# digital.net
KiCad netlist of a schematic drawn in EAGLE
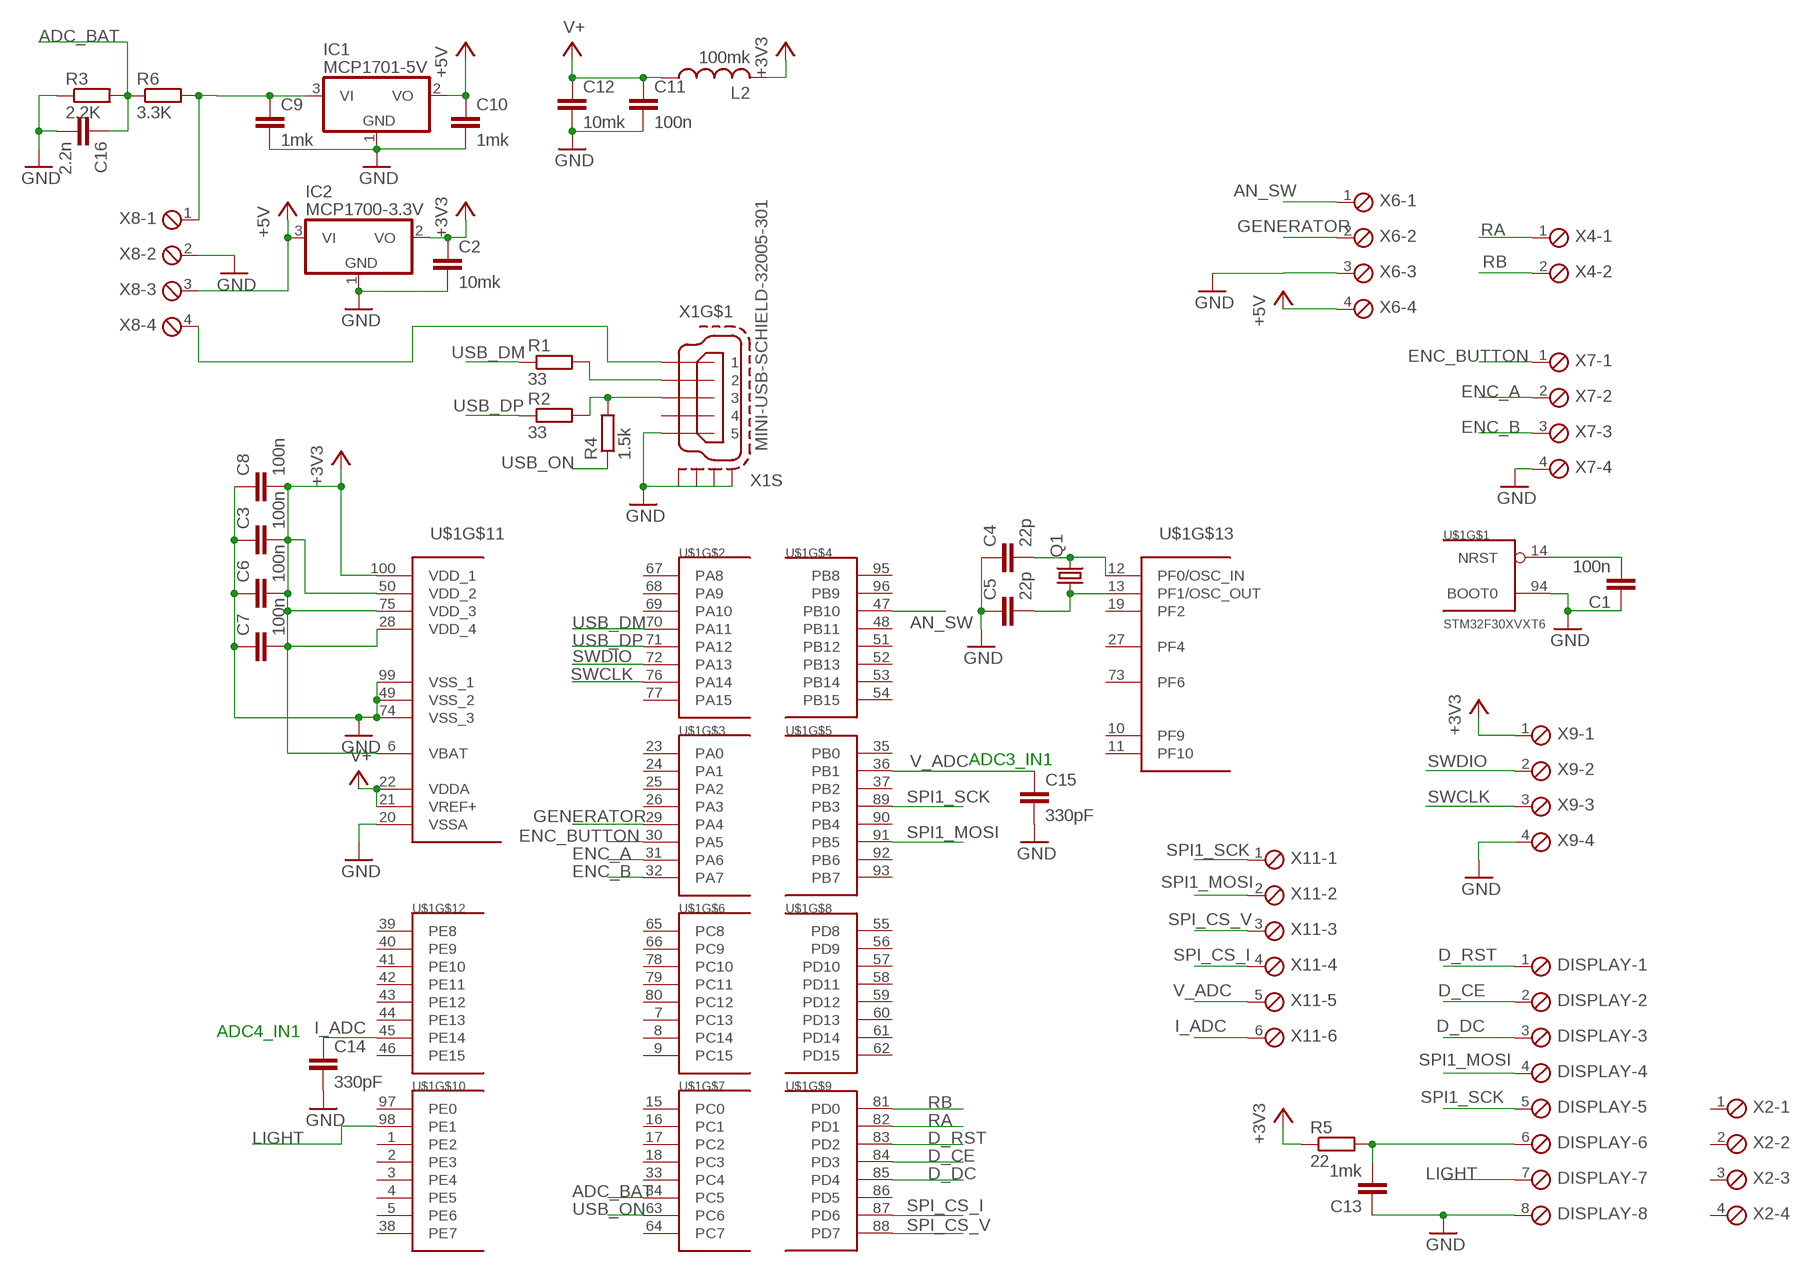
[diagram p0: schematic, sheet 1]

(export (version "E")
  (design (tool "Eeschema 10.0.6"))
  (components
    (comp (ref "C1")
      (value "100n")
      (footprint "eagle-import:C0603")
      (libsource (lib "eagle-import") (part "C-EUC0603"))
    )
    (comp (ref "C2")
      (value "10mk")
      (footprint "eagle-import:C0805")
      (libsource (lib "eagle-import") (part "C-EUC0805"))
    )
    (comp (ref "C3")
      (value "100n")
      (footprint "eagle-import:C0603")
      (libsource (lib "eagle-import") (part "C-EUC0603"))
    )
    (comp (ref "C4")
      (value "22p")
      (footprint "eagle-import:C0805")
      (libsource (lib "eagle-import") (part "C-EUC0805"))
    )
    (comp (ref "C5")
      (value "22p")
      (footprint "eagle-import:C0805")
      (libsource (lib "eagle-import") (part "C-EUC0805"))
    )
    (comp (ref "C6")
      (value "100n")
      (footprint "eagle-import:C0603")
      (libsource (lib "eagle-import") (part "C-EUC0603"))
    )
    (comp (ref "C7")
      (value "100n")
      (footprint "eagle-import:C0603")
      (libsource (lib "eagle-import") (part "C-EUC0603"))
    )
    (comp (ref "C8")
      (value "100n")
      (footprint "eagle-import:C0603")
      (libsource (lib "eagle-import") (part "C-EUC0603"))
    )
    (comp (ref "C9")
      (value "1mk")
      (footprint "eagle-import:C0603")
      (libsource (lib "eagle-import") (part "C-EUC0603"))
    )
    (comp (ref "C10")
      (value "1mk")
      (footprint "eagle-import:C0603")
      (libsource (lib "eagle-import") (part "C-EUC0603"))
    )
    (comp (ref "C11")
      (value "100n")
      (footprint "eagle-import:C0603")
      (libsource (lib "eagle-import") (part "C-EUC0603"))
    )
    (comp (ref "C12")
      (value "10mk")
      (footprint "eagle-import:C0805")
      (libsource (lib "eagle-import") (part "C-EUC0805"))
    )
    (comp (ref "C13")
      (value "1mk")
      (footprint "eagle-import:C0603")
      (libsource (lib "eagle-import") (part "C-EUC0603"))
    )
    (comp (ref "C14")
      (value "330pF")
      (footprint "eagle-import:C0805")
      (libsource (lib "eagle-import") (part "C-EUC0805"))
    )
    (comp (ref "C15")
      (value "330pF")
      (footprint "eagle-import:C0805")
      (libsource (lib "eagle-import") (part "C-EUC0805"))
    )
    (comp (ref "C16")
      (value "2.2n")
      (footprint "eagle-import:C0805")
      (libsource (lib "eagle-import") (part "C-EUC0805"))
    )
    (comp (ref "DISPLAY")
      (value "MPT8")
      (footprint "eagle-import:8POL254")
      (libsource (lib "eagle-import") (part "MPT8"))
    )
    (comp (ref "IC1")
      (value "MCP1701-5V")
      (footprint "eagle-import:SOT23")
      (libsource (lib "eagle-import") (part "MCP1703CB"))
    )
    (comp (ref "IC2")
      (value "MCP1700-3.3V")
      (footprint "eagle-import:SOT23")
      (libsource (lib "eagle-import") (part "MCP1703CB"))
    )
    (comp (ref "L2")
      (value "100mk")
      (footprint "eagle-import:0204_7")
      (libsource (lib "eagle-import") (part "L-US0204/7"))
    )
    (comp (ref "Q1")
      (value "CRYSTALHC49UP")
      (footprint "eagle-import:HC49UP")
      (libsource (lib "eagle-import") (part "CRYSTALHC49UP"))
    )
    (comp (ref "R1")
      (value "33")
      (footprint "eagle-import:R0603")
      (libsource (lib "eagle-import") (part "R-EU_R0603"))
    )
    (comp (ref "R2")
      (value "33")
      (footprint "eagle-import:R0603")
      (libsource (lib "eagle-import") (part "R-EU_R0603"))
    )
    (comp (ref "R3")
      (value "2.2K")
      (footprint "eagle-import:R0603")
      (libsource (lib "eagle-import") (part "R-EU_R0603"))
    )
    (comp (ref "R4")
      (value "1.5k")
      (footprint "eagle-import:R0603")
      (libsource (lib "eagle-import") (part "R-EU_R0603"))
    )
    (comp (ref "R5")
      (value "22")
      (footprint "eagle-import:R0603")
      (libsource (lib "eagle-import") (part "R-EU_R0603"))
    )
    (comp (ref "R6")
      (value "3.3K")
      (footprint "eagle-import:R0603")
      (libsource (lib "eagle-import") (part "R-EU_R0603"))
    )
    (comp (ref "U$1")
      (value "STM32F30XVXT6")
      (footprint "eagle-import:TQFP100")
      (libsource (lib "eagle-import") (part "STM32F30XVXT6"))
    )
    (comp (ref "X1")
      (value "MINI-USB-SCHIELD-32005-301")
      (footprint "eagle-import:32005-301")
      (libsource (lib "eagle-import") (part "MINI-USB-SCHIELD-32005-301"))
    )
    (comp (ref "X2")
      (value "MPT4")
      (footprint "eagle-import:4POL254")
      (libsource (lib "eagle-import") (part "MPT4"))
    )
    (comp (ref "X4")
      (value "MPT2")
      (footprint "eagle-import:2POL254")
      (libsource (lib "eagle-import") (part "MPT2"))
    )
    (comp (ref "X6")
      (value "MPT4")
      (footprint "eagle-import:4POL254")
      (libsource (lib "eagle-import") (part "MPT4"))
    )
    (comp (ref "X7")
      (value "MPT4")
      (footprint "eagle-import:4POL254")
      (libsource (lib "eagle-import") (part "MPT4"))
    )
    (comp (ref "X8")
      (value "MPT4")
      (footprint "eagle-import:4POL254")
      (libsource (lib "eagle-import") (part "MPT4"))
    )
    (comp (ref "X9")
      (value "MPT4")
      (footprint "eagle-import:4POL254")
      (libsource (lib "eagle-import") (part "MPT4"))
    )
    (comp (ref "X11")
      (value "MPT6")
      (footprint "eagle-import:6POL254")
      (libsource (lib "eagle-import") (part "MPT6"))
    )
  )
  (nets
    (net (code "1") (name "+3V3") (class "Default")
      (node (ref "C2") (pin "1") (pinfunction "1_1") (pintype "passive"))
      (node (ref "C3") (pin "2") (pinfunction "2_2") (pintype "passive"))
      (node (ref "C6") (pin "2") (pinfunction "2_2") (pintype "passive"))
      (node (ref "C7") (pin "2") (pinfunction "2_2") (pintype "passive"))
      (node (ref "C8") (pin "2") (pinfunction "2_2") (pintype "passive"))
      (node (ref "IC2") (pin "2") (pinfunction "VO_2") (pintype "passive"))
      (node (ref "L2") (pin "2") (pinfunction "2_2") (pintype "passive"))
      (node (ref "R5") (pin "1") (pinfunction "1_1") (pintype "passive"))
      (node (ref "U$1") (pin "100") (pinfunction "VDD_1_100") (pintype "bidirectional"))
      (node (ref "U$1") (pin "28") (pinfunction "VDD_4_28") (pintype "bidirectional"))
      (node (ref "U$1") (pin "50") (pinfunction "VDD_2_50") (pintype "bidirectional"))
      (node (ref "U$1") (pin "6") (pinfunction "VBAT_6") (pintype "bidirectional"))
      (node (ref "U$1") (pin "75") (pinfunction "VDD_3_75") (pintype "bidirectional"))
      (node (ref "X9") (pin "1") (pinfunction "1_1") (pintype "passive"))
    )
    (net (code "2") (name "+5V") (class "Default")
      (node (ref "C10") (pin "1") (pinfunction "1_1") (pintype "passive"))
      (node (ref "IC1") (pin "2") (pinfunction "VO_2") (pintype "passive"))
      (node (ref "IC2") (pin "3") (pinfunction "VI_3") (pintype "input"))
      (node (ref "X6") (pin "4") (pinfunction "1_4") (pintype "passive"))
      (node (ref "X8") (pin "3") (pinfunction "1_3") (pintype "passive"))
    )
    (net (code "3") (name "/ADC_BAT") (class "Default")
      (node (ref "C16") (pin "1") (pinfunction "1_1") (pintype "passive"))
      (node (ref "R3") (pin "2") (pinfunction "2_2") (pintype "passive"))
      (node (ref "R6") (pin "1") (pinfunction "1_1") (pintype "passive"))
      (node (ref "U$1") (pin "34") (pinfunction "PC5_34") (pintype "bidirectional"))
    )
    (net (code "4") (name "/AN_SW") (class "Default")
      (node (ref "U$1") (pin "47") (pinfunction "PB10_47") (pintype "bidirectional"))
      (node (ref "X6") (pin "1") (pinfunction "1_1") (pintype "passive"))
    )
    (net (code "5") (name "/D_CE") (class "Default")
      (node (ref "DISPLAY") (pin "2") (pinfunction "1_2") (pintype "passive"))
      (node (ref "U$1") (pin "84") (pinfunction "PD3_84") (pintype "bidirectional"))
    )
    (net (code "6") (name "/D_DC") (class "Default")
      (node (ref "DISPLAY") (pin "3") (pinfunction "1_3") (pintype "passive"))
      (node (ref "U$1") (pin "85") (pinfunction "PD4_85") (pintype "bidirectional"))
    )
    (net (code "7") (name "/D_RST") (class "Default")
      (node (ref "DISPLAY") (pin "1") (pinfunction "1_1") (pintype "passive"))
      (node (ref "U$1") (pin "83") (pinfunction "PD2_83") (pintype "bidirectional"))
    )
    (net (code "8") (name "/ENC_A") (class "Default")
      (node (ref "U$1") (pin "31") (pinfunction "PA6_31") (pintype "bidirectional"))
      (node (ref "X7") (pin "2") (pinfunction "1_2") (pintype "passive"))
    )
    (net (code "9") (name "/ENC_B") (class "Default")
      (node (ref "U$1") (pin "32") (pinfunction "PA7_32") (pintype "bidirectional"))
      (node (ref "X7") (pin "3") (pinfunction "1_3") (pintype "passive"))
    )
    (net (code "10") (name "/ENC_BUTTON") (class "Default")
      (node (ref "U$1") (pin "30") (pinfunction "PA5_30") (pintype "bidirectional"))
      (node (ref "X7") (pin "1") (pinfunction "1_1") (pintype "passive"))
    )
    (net (code "11") (name "/GENERATOR") (class "Default")
      (node (ref "U$1") (pin "29") (pinfunction "PA4_29") (pintype "bidirectional"))
      (node (ref "X6") (pin "2") (pinfunction "1_2") (pintype "passive"))
    )
    (net (code "12") (name "/I_ADC") (class "Default")
      (node (ref "C14") (pin "1") (pinfunction "1_1") (pintype "passive"))
      (node (ref "U$1") (pin "45") (pinfunction "PE14_45") (pintype "bidirectional"))
      (node (ref "X11") (pin "6") (pinfunction "1_6") (pintype "passive"))
    )
    (net (code "13") (name "/LIGHT") (class "Default")
      (node (ref "DISPLAY") (pin "7") (pinfunction "1_7") (pintype "passive"))
      (node (ref "U$1") (pin "98") (pinfunction "PE1_98") (pintype "bidirectional"))
    )
    (net (code "14") (name "/RA") (class "Default")
      (node (ref "U$1") (pin "82") (pinfunction "PD1_82") (pintype "bidirectional"))
      (node (ref "X4") (pin "1") (pinfunction "1_1") (pintype "passive"))
    )
    (net (code "15") (name "/RB") (class "Default")
      (node (ref "U$1") (pin "81") (pinfunction "PD0_81") (pintype "bidirectional"))
      (node (ref "X4") (pin "2") (pinfunction "1_2") (pintype "passive"))
    )
    (net (code "16") (name "/SPI1_MOSI") (class "Default")
      (node (ref "DISPLAY") (pin "4") (pinfunction "1_4") (pintype "passive"))
      (node (ref "U$1") (pin "91") (pinfunction "PB5_91") (pintype "bidirectional"))
      (node (ref "X11") (pin "2") (pinfunction "1_2") (pintype "passive"))
    )
    (net (code "17") (name "/SPI1_SCK") (class "Default")
      (node (ref "DISPLAY") (pin "5") (pinfunction "1_5") (pintype "passive"))
      (node (ref "U$1") (pin "89") (pinfunction "PB3_89") (pintype "bidirectional"))
      (node (ref "X11") (pin "1") (pinfunction "1_1") (pintype "passive"))
    )
    (net (code "18") (name "/SPI_CS_I") (class "Default")
      (node (ref "U$1") (pin "87") (pinfunction "PD6_87") (pintype "bidirectional"))
      (node (ref "X11") (pin "4") (pinfunction "1_4") (pintype "passive"))
    )
    (net (code "19") (name "/SPI_CS_V") (class "Default")
      (node (ref "U$1") (pin "88") (pinfunction "PD7_88") (pintype "bidirectional"))
      (node (ref "X11") (pin "3") (pinfunction "1_3") (pintype "passive"))
    )
    (net (code "20") (name "/SWCLK") (class "Default")
      (node (ref "U$1") (pin "76") (pinfunction "PA14_76") (pintype "bidirectional"))
      (node (ref "X9") (pin "3") (pinfunction "1_3") (pintype "passive"))
    )
    (net (code "21") (name "/SWDIO") (class "Default")
      (node (ref "U$1") (pin "72") (pinfunction "PA13_72") (pintype "bidirectional"))
      (node (ref "X9") (pin "2") (pinfunction "1_2") (pintype "passive"))
    )
    (net (code "22") (name "/USB_DM") (class "Default")
      (node (ref "R1") (pin "1") (pinfunction "1_1") (pintype "passive"))
      (node (ref "U$1") (pin "70") (pinfunction "PA11_70") (pintype "bidirectional"))
    )
    (net (code "23") (name "/USB_DP") (class "Default")
      (node (ref "R2") (pin "1") (pinfunction "1_1") (pintype "passive"))
      (node (ref "U$1") (pin "71") (pinfunction "PA12_71") (pintype "bidirectional"))
    )
    (net (code "24") (name "/USB_ON") (class "Default")
      (node (ref "R4") (pin "1") (pinfunction "1_1") (pintype "passive"))
      (node (ref "U$1") (pin "63") (pinfunction "PC6_63") (pintype "bidirectional"))
    )
    (net (code "25") (name "/V_ADC") (class "Default")
      (node (ref "C15") (pin "1") (pinfunction "1_1") (pintype "passive"))
      (node (ref "U$1") (pin "36") (pinfunction "PB1_36") (pintype "bidirectional"))
      (node (ref "X11") (pin "5") (pinfunction "1_5") (pintype "passive"))
    )
    (net (code "26") (name "GND") (class "Default")
      (node (ref "C1") (pin "1") (pinfunction "1_1") (pintype "passive"))
      (node (ref "C10") (pin "2") (pinfunction "2_2") (pintype "passive"))
      (node (ref "C11") (pin "2") (pinfunction "2_2") (pintype "passive"))
      (node (ref "C12") (pin "2") (pinfunction "2_2") (pintype "passive"))
      (node (ref "C13") (pin "1") (pinfunction "1_1") (pintype "passive"))
      (node (ref "C14") (pin "2") (pinfunction "2_2") (pintype "passive"))
      (node (ref "C15") (pin "2") (pinfunction "2_2") (pintype "passive"))
      (node (ref "C16") (pin "2") (pinfunction "2_2") (pintype "passive"))
      (node (ref "C2") (pin "2") (pinfunction "2_2") (pintype "passive"))
      (node (ref "C3") (pin "1") (pinfunction "1_1") (pintype "passive"))
      (node (ref "C4") (pin "1") (pinfunction "1_1") (pintype "passive"))
      (node (ref "C5") (pin "1") (pinfunction "1_1") (pintype "passive"))
      (node (ref "C6") (pin "1") (pinfunction "1_1") (pintype "passive"))
      (node (ref "C7") (pin "1") (pinfunction "1_1") (pintype "passive"))
      (node (ref "C8") (pin "1") (pinfunction "1_1") (pintype "passive"))
      (node (ref "C9") (pin "2") (pinfunction "2_2") (pintype "passive"))
      (node (ref "DISPLAY") (pin "8") (pinfunction "1_8") (pintype "passive"))
      (node (ref "IC1") (pin "1") (pinfunction "GND_1") (pintype "passive"))
      (node (ref "IC2") (pin "1") (pinfunction "GND_1") (pintype "passive"))
      (node (ref "R3") (pin "1") (pinfunction "1_1") (pintype "passive"))
      (node (ref "U$1") (pin "20") (pinfunction "VSSA_20") (pintype "bidirectional"))
      (node (ref "U$1") (pin "49") (pinfunction "VSS_2_49") (pintype "bidirectional"))
      (node (ref "U$1") (pin "74") (pinfunction "VSS_3_74") (pintype "bidirectional"))
      (node (ref "U$1") (pin "94") (pinfunction "BOOT0_94") (pintype "input"))
      (node (ref "U$1") (pin "99") (pinfunction "VSS_1_99") (pintype "bidirectional"))
      (node (ref "X1") (pin "5") (pinfunction "5_5") (pintype "passive"))
      (node (ref "X1") (pin "M1") (pinfunction "S1_M1") (pintype "passive"))
      (node (ref "X1") (pin "M2") (pinfunction "S2_M2") (pintype "passive"))
      (node (ref "X1") (pin "M3") (pinfunction "S3_M3") (pintype "passive"))
      (node (ref "X1") (pin "M4") (pinfunction "S4_M4") (pintype "passive"))
      (node (ref "X6") (pin "3") (pinfunction "1_3") (pintype "passive"))
      (node (ref "X7") (pin "4") (pinfunction "1_4") (pintype "passive"))
      (node (ref "X8") (pin "2") (pinfunction "1_2") (pintype "passive"))
      (node (ref "X9") (pin "4") (pinfunction "1_4") (pintype "passive"))
    )
    (net (code "27") (name "Net-(DISPLAYF-1)") (class "Default")
      (node (ref "C13") (pin "2") (pinfunction "2_2") (pintype "passive"))
      (node (ref "DISPLAY") (pin "6") (pinfunction "1_6") (pintype "passive"))
      (node (ref "R5") (pin "2") (pinfunction "2_2") (pintype "passive"))
    )
    (net (code "28") (name "Net-(IC1-VI)") (class "Default")
      (node (ref "C9") (pin "1") (pinfunction "1_1") (pintype "passive"))
      (node (ref "IC1") (pin "3") (pinfunction "VI_3") (pintype "input"))
      (node (ref "R6") (pin "2") (pinfunction "2_2") (pintype "passive"))
      (node (ref "X8") (pin "1") (pinfunction "1_1") (pintype "passive"))
    )
    (net (code "29") (name "Net-(R1-Pad2)") (class "Default")
      (node (ref "R1") (pin "2") (pinfunction "2_2") (pintype "passive"))
      (node (ref "X1") (pin "2") (pinfunction "2_2") (pintype "passive"))
    )
    (net (code "30") (name "Net-(R2-Pad2)") (class "Default")
      (node (ref "R2") (pin "2") (pinfunction "2_2") (pintype "passive"))
      (node (ref "R4") (pin "2") (pinfunction "2_2") (pintype "passive"))
      (node (ref "X1") (pin "3") (pinfunction "3_3") (pintype "passive"))
    )
    (net (code "31") (name "Net-(U$1A-NRST)") (class "Default")
      (node (ref "C1") (pin "2") (pinfunction "2_2") (pintype "passive"))
      (node (ref "U$1") (pin "14") (pinfunction "NRST_14") (pintype "input"))
    )
    (net (code "32") (name "Net-(U$1E-PF0{slash}OSC_IN)") (class "Default")
      (node (ref "C4") (pin "2") (pinfunction "2_2") (pintype "passive"))
      (node (ref "Q1") (pin "2") (pinfunction "2_2") (pintype "passive"))
      (node (ref "U$1") (pin "12") (pinfunction "PF0/OSC_IN_12") (pintype "bidirectional"))
    )
    (net (code "33") (name "Net-(U$1E-PF1{slash}OSC_OUT)") (class "Default")
      (node (ref "C5") (pin "2") (pinfunction "2_2") (pintype "passive"))
      (node (ref "Q1") (pin "1") (pinfunction "1_1") (pintype "passive"))
      (node (ref "U$1") (pin "13") (pinfunction "PF1/OSC_OUT_13") (pintype "bidirectional"))
    )
    (net (code "34") (name "Net-(X8D-1)") (class "Default")
      (node (ref "X1") (pin "1") (pinfunction "1_1") (pintype "passive"))
      (node (ref "X8") (pin "4") (pinfunction "1_4") (pintype "passive"))
    )
    (net (code "35") (name "V+") (class "Default")
      (node (ref "C11") (pin "1") (pinfunction "1_1") (pintype "passive"))
      (node (ref "C12") (pin "1") (pinfunction "1_1") (pintype "passive"))
      (node (ref "L2") (pin "1") (pinfunction "1_1") (pintype "passive"))
      (node (ref "U$1") (pin "21") (pinfunction "VREF+_21") (pintype "bidirectional"))
      (node (ref "U$1") (pin "22") (pinfunction "VDDA_22") (pintype "bidirectional"))
    )
    (net (code "36") (name "unconnected-(U$1B-PE0-Pad97)") (class "Default")
      (node (ref "U$1") (pin "97") (pinfunction "PE0_97") (pintype "bidirectional"))
    )
    (net (code "37") (name "unconnected-(U$1B-PE2-Pad1)") (class "Default")
      (node (ref "U$1") (pin "1") (pinfunction "PE2_1") (pintype "bidirectional"))
    )
    (net (code "38") (name "unconnected-(U$1B-PE3-Pad2)") (class "Default")
      (node (ref "U$1") (pin "2") (pinfunction "PE3_2") (pintype "bidirectional"))
    )
    (net (code "39") (name "unconnected-(U$1B-PE4-Pad3)") (class "Default")
      (node (ref "U$1") (pin "3") (pinfunction "PE4_3") (pintype "bidirectional"))
    )
    (net (code "40") (name "unconnected-(U$1B-PE5-Pad4)") (class "Default")
      (node (ref "U$1") (pin "4") (pinfunction "PE5_4") (pintype "bidirectional"))
    )
    (net (code "41") (name "unconnected-(U$1B-PE6-Pad5)") (class "Default")
      (node (ref "U$1") (pin "5") (pinfunction "PE6_5") (pintype "bidirectional"))
    )
    (net (code "42") (name "unconnected-(U$1B-PE7-Pad38)") (class "Default")
      (node (ref "U$1") (pin "38") (pinfunction "PE7_38") (pintype "bidirectional"))
    )
    (net (code "43") (name "unconnected-(U$1D-PE8-Pad39)") (class "Default")
      (node (ref "U$1") (pin "39") (pinfunction "PE8_39") (pintype "bidirectional"))
    )
    (net (code "44") (name "unconnected-(U$1D-PE9-Pad40)") (class "Default")
      (node (ref "U$1") (pin "40") (pinfunction "PE9_40") (pintype "bidirectional"))
    )
    (net (code "45") (name "unconnected-(U$1D-PE10-Pad41)") (class "Default")
      (node (ref "U$1") (pin "41") (pinfunction "PE10_41") (pintype "bidirectional"))
    )
    (net (code "46") (name "unconnected-(U$1D-PE11-Pad42)") (class "Default")
      (node (ref "U$1") (pin "42") (pinfunction "PE11_42") (pintype "bidirectional"))
    )
    (net (code "47") (name "unconnected-(U$1D-PE12-Pad43)") (class "Default")
      (node (ref "U$1") (pin "43") (pinfunction "PE12_43") (pintype "bidirectional"))
    )
    (net (code "48") (name "unconnected-(U$1D-PE13-Pad44)") (class "Default")
      (node (ref "U$1") (pin "44") (pinfunction "PE13_44") (pintype "bidirectional"))
    )
    (net (code "49") (name "unconnected-(U$1D-PE15-Pad46)") (class "Default")
      (node (ref "U$1") (pin "46") (pinfunction "PE15_46") (pintype "bidirectional"))
    )
    (net (code "50") (name "unconnected-(U$1E-PF2-Pad19)") (class "Default")
      (node (ref "U$1") (pin "19") (pinfunction "PF2_19") (pintype "bidirectional"))
    )
    (net (code "51") (name "unconnected-(U$1E-PF4-Pad27)") (class "Default")
      (node (ref "U$1") (pin "27") (pinfunction "PF4_27") (pintype "bidirectional"))
    )
    (net (code "52") (name "unconnected-(U$1E-PF6-Pad73)") (class "Default")
      (node (ref "U$1") (pin "73") (pinfunction "PF6_73") (pintype "bidirectional"))
    )
    (net (code "53") (name "unconnected-(U$1E-PF9-Pad10)") (class "Default")
      (node (ref "U$1") (pin "10") (pinfunction "PF9_10") (pintype "bidirectional"))
    )
    (net (code "54") (name "unconnected-(U$1E-PF10-Pad11)") (class "Default")
      (node (ref "U$1") (pin "11") (pinfunction "PF10_11") (pintype "bidirectional"))
    )
    (net (code "55") (name "unconnected-(U$1F-PA8-Pad67)") (class "Default")
      (node (ref "U$1") (pin "67") (pinfunction "PA8_67") (pintype "bidirectional"))
    )
    (net (code "56") (name "unconnected-(U$1F-PA9-Pad68)") (class "Default")
      (node (ref "U$1") (pin "68") (pinfunction "PA9_68") (pintype "bidirectional"))
    )
    (net (code "57") (name "unconnected-(U$1F-PA10-Pad69)") (class "Default")
      (node (ref "U$1") (pin "69") (pinfunction "PA10_69") (pintype "bidirectional"))
    )
    (net (code "58") (name "unconnected-(U$1F-PA15-Pad77)") (class "Default")
      (node (ref "U$1") (pin "77") (pinfunction "PA15_77") (pintype "bidirectional"))
    )
    (net (code "59") (name "unconnected-(U$1G-PA0-Pad23)") (class "Default")
      (node (ref "U$1") (pin "23") (pinfunction "PA0_23") (pintype "bidirectional"))
    )
    (net (code "60") (name "unconnected-(U$1G-PA1-Pad24)") (class "Default")
      (node (ref "U$1") (pin "24") (pinfunction "PA1_24") (pintype "bidirectional"))
    )
    (net (code "61") (name "unconnected-(U$1G-PA2-Pad25)") (class "Default")
      (node (ref "U$1") (pin "25") (pinfunction "PA2_25") (pintype "bidirectional"))
    )
    (net (code "62") (name "unconnected-(U$1G-PA3-Pad26)") (class "Default")
      (node (ref "U$1") (pin "26") (pinfunction "PA3_26") (pintype "bidirectional"))
    )
    (net (code "63") (name "unconnected-(U$1H-PB8-Pad95)") (class "Default")
      (node (ref "U$1") (pin "95") (pinfunction "PB8_95") (pintype "bidirectional"))
    )
    (net (code "64") (name "unconnected-(U$1H-PB9-Pad96)") (class "Default")
      (node (ref "U$1") (pin "96") (pinfunction "PB9_96") (pintype "bidirectional"))
    )
    (net (code "65") (name "unconnected-(U$1H-PB11-Pad48)") (class "Default")
      (node (ref "U$1") (pin "48") (pinfunction "PB11_48") (pintype "bidirectional"))
    )
    (net (code "66") (name "unconnected-(U$1H-PB12-Pad51)") (class "Default")
      (node (ref "U$1") (pin "51") (pinfunction "PB12_51") (pintype "bidirectional"))
    )
    (net (code "67") (name "unconnected-(U$1H-PB13-Pad52)") (class "Default")
      (node (ref "U$1") (pin "52") (pinfunction "PB13_52") (pintype "bidirectional"))
    )
    (net (code "68") (name "unconnected-(U$1H-PB14-Pad53)") (class "Default")
      (node (ref "U$1") (pin "53") (pinfunction "PB14_53") (pintype "bidirectional"))
    )
    (net (code "69") (name "unconnected-(U$1H-PB15-Pad54)") (class "Default")
      (node (ref "U$1") (pin "54") (pinfunction "PB15_54") (pintype "bidirectional"))
    )
    (net (code "70") (name "unconnected-(U$1I-PB0-Pad35)") (class "Default")
      (node (ref "U$1") (pin "35") (pinfunction "PB0_35") (pintype "bidirectional"))
    )
    (net (code "71") (name "unconnected-(U$1I-PB2-Pad37)") (class "Default")
      (node (ref "U$1") (pin "37") (pinfunction "PB2_37") (pintype "bidirectional"))
    )
    (net (code "72") (name "unconnected-(U$1I-PB4-Pad90)") (class "Default")
      (node (ref "U$1") (pin "90") (pinfunction "PB4_90") (pintype "bidirectional"))
    )
    (net (code "73") (name "unconnected-(U$1I-PB6-Pad92)") (class "Default")
      (node (ref "U$1") (pin "92") (pinfunction "PB6_92") (pintype "bidirectional"))
    )
    (net (code "74") (name "unconnected-(U$1I-PB7-Pad93)") (class "Default")
      (node (ref "U$1") (pin "93") (pinfunction "PB7_93") (pintype "bidirectional"))
    )
    (net (code "75") (name "unconnected-(U$1J-PC8-Pad65)") (class "Default")
      (node (ref "U$1") (pin "65") (pinfunction "PC8_65") (pintype "bidirectional"))
    )
    (net (code "76") (name "unconnected-(U$1J-PC9-Pad66)") (class "Default")
      (node (ref "U$1") (pin "66") (pinfunction "PC9_66") (pintype "bidirectional"))
    )
    (net (code "77") (name "unconnected-(U$1J-PC10-Pad78)") (class "Default")
      (node (ref "U$1") (pin "78") (pinfunction "PC10_78") (pintype "bidirectional"))
    )
    (net (code "78") (name "unconnected-(U$1J-PC11-Pad79)") (class "Default")
      (node (ref "U$1") (pin "79") (pinfunction "PC11_79") (pintype "bidirectional"))
    )
    (net (code "79") (name "unconnected-(U$1J-PC12-Pad80)") (class "Default")
      (node (ref "U$1") (pin "80") (pinfunction "PC12_80") (pintype "bidirectional"))
    )
    (net (code "80") (name "unconnected-(U$1J-PC13-Pad7)") (class "Default")
      (node (ref "U$1") (pin "7") (pinfunction "PC13_7") (pintype "bidirectional"))
    )
    (net (code "81") (name "unconnected-(U$1J-PC14-Pad8)") (class "Default")
      (node (ref "U$1") (pin "8") (pinfunction "PC14_8") (pintype "bidirectional"))
    )
    (net (code "82") (name "unconnected-(U$1J-PC15-Pad9)") (class "Default")
      (node (ref "U$1") (pin "9") (pinfunction "PC15_9") (pintype "bidirectional"))
    )
    (net (code "83") (name "unconnected-(U$1K-PC0-Pad15)") (class "Default")
      (node (ref "U$1") (pin "15") (pinfunction "PC0_15") (pintype "bidirectional"))
    )
    (net (code "84") (name "unconnected-(U$1K-PC1-Pad16)") (class "Default")
      (node (ref "U$1") (pin "16") (pinfunction "PC1_16") (pintype "bidirectional"))
    )
    (net (code "85") (name "unconnected-(U$1K-PC2-Pad17)") (class "Default")
      (node (ref "U$1") (pin "17") (pinfunction "PC2_17") (pintype "bidirectional"))
    )
    (net (code "86") (name "unconnected-(U$1K-PC3-Pad18)") (class "Default")
      (node (ref "U$1") (pin "18") (pinfunction "PC3_18") (pintype "bidirectional"))
    )
    (net (code "87") (name "unconnected-(U$1K-PC4-Pad33)") (class "Default")
      (node (ref "U$1") (pin "33") (pinfunction "PC4_33") (pintype "bidirectional"))
    )
    (net (code "88") (name "unconnected-(U$1K-PC7-Pad64)") (class "Default")
      (node (ref "U$1") (pin "64") (pinfunction "PC7_64") (pintype "bidirectional"))
    )
    (net (code "89") (name "unconnected-(U$1L-PD8-Pad55)") (class "Default")
      (node (ref "U$1") (pin "55") (pinfunction "PD8_55") (pintype "bidirectional"))
    )
    (net (code "90") (name "unconnected-(U$1L-PD9-Pad56)") (class "Default")
      (node (ref "U$1") (pin "56") (pinfunction "PD9_56") (pintype "bidirectional"))
    )
    (net (code "91") (name "unconnected-(U$1L-PD10-Pad57)") (class "Default")
      (node (ref "U$1") (pin "57") (pinfunction "PD10_57") (pintype "bidirectional"))
    )
    (net (code "92") (name "unconnected-(U$1L-PD11-Pad58)") (class "Default")
      (node (ref "U$1") (pin "58") (pinfunction "PD11_58") (pintype "bidirectional"))
    )
    (net (code "93") (name "unconnected-(U$1L-PD12-Pad59)") (class "Default")
      (node (ref "U$1") (pin "59") (pinfunction "PD12_59") (pintype "bidirectional"))
    )
    (net (code "94") (name "unconnected-(U$1L-PD13-Pad60)") (class "Default")
      (node (ref "U$1") (pin "60") (pinfunction "PD13_60") (pintype "bidirectional"))
    )
    (net (code "95") (name "unconnected-(U$1L-PD14-Pad61)") (class "Default")
      (node (ref "U$1") (pin "61") (pinfunction "PD14_61") (pintype "bidirectional"))
    )
    (net (code "96") (name "unconnected-(U$1L-PD15-Pad62)") (class "Default")
      (node (ref "U$1") (pin "62") (pinfunction "PD15_62") (pintype "bidirectional"))
    )
    (net (code "97") (name "unconnected-(U$1M-PD5-Pad86)") (class "Default")
      (node (ref "U$1") (pin "86") (pinfunction "PD5_86") (pintype "bidirectional"))
    )
    (net (code "98") (name "unconnected-(X1-Pad4)") (class "Default")
      (node (ref "X1") (pin "4") (pinfunction "4_4") (pintype "passive"))
    )
    (net (code "99") (name "unconnected-(X2-Pad1)") (class "Default")
      (node (ref "X2") (pin "1") (pinfunction "1_1") (pintype "passive"))
    )
    (net (code "100") (name "unconnected-(X2B-1-Pad2)") (class "Default")
      (node (ref "X2") (pin "2") (pinfunction "1_2") (pintype "passive"))
    )
    (net (code "101") (name "unconnected-(X2C-1-Pad3)") (class "Default")
      (node (ref "X2") (pin "3") (pinfunction "1_3") (pintype "passive"))
    )
    (net (code "102") (name "unconnected-(X2D-1-Pad4)") (class "Default")
      (node (ref "X2") (pin "4") (pinfunction "1_4") (pintype "passive"))
    )
  )
)
